# Output_Distribution.net
KiCad netlist of a schematic drawn in Altium Designer
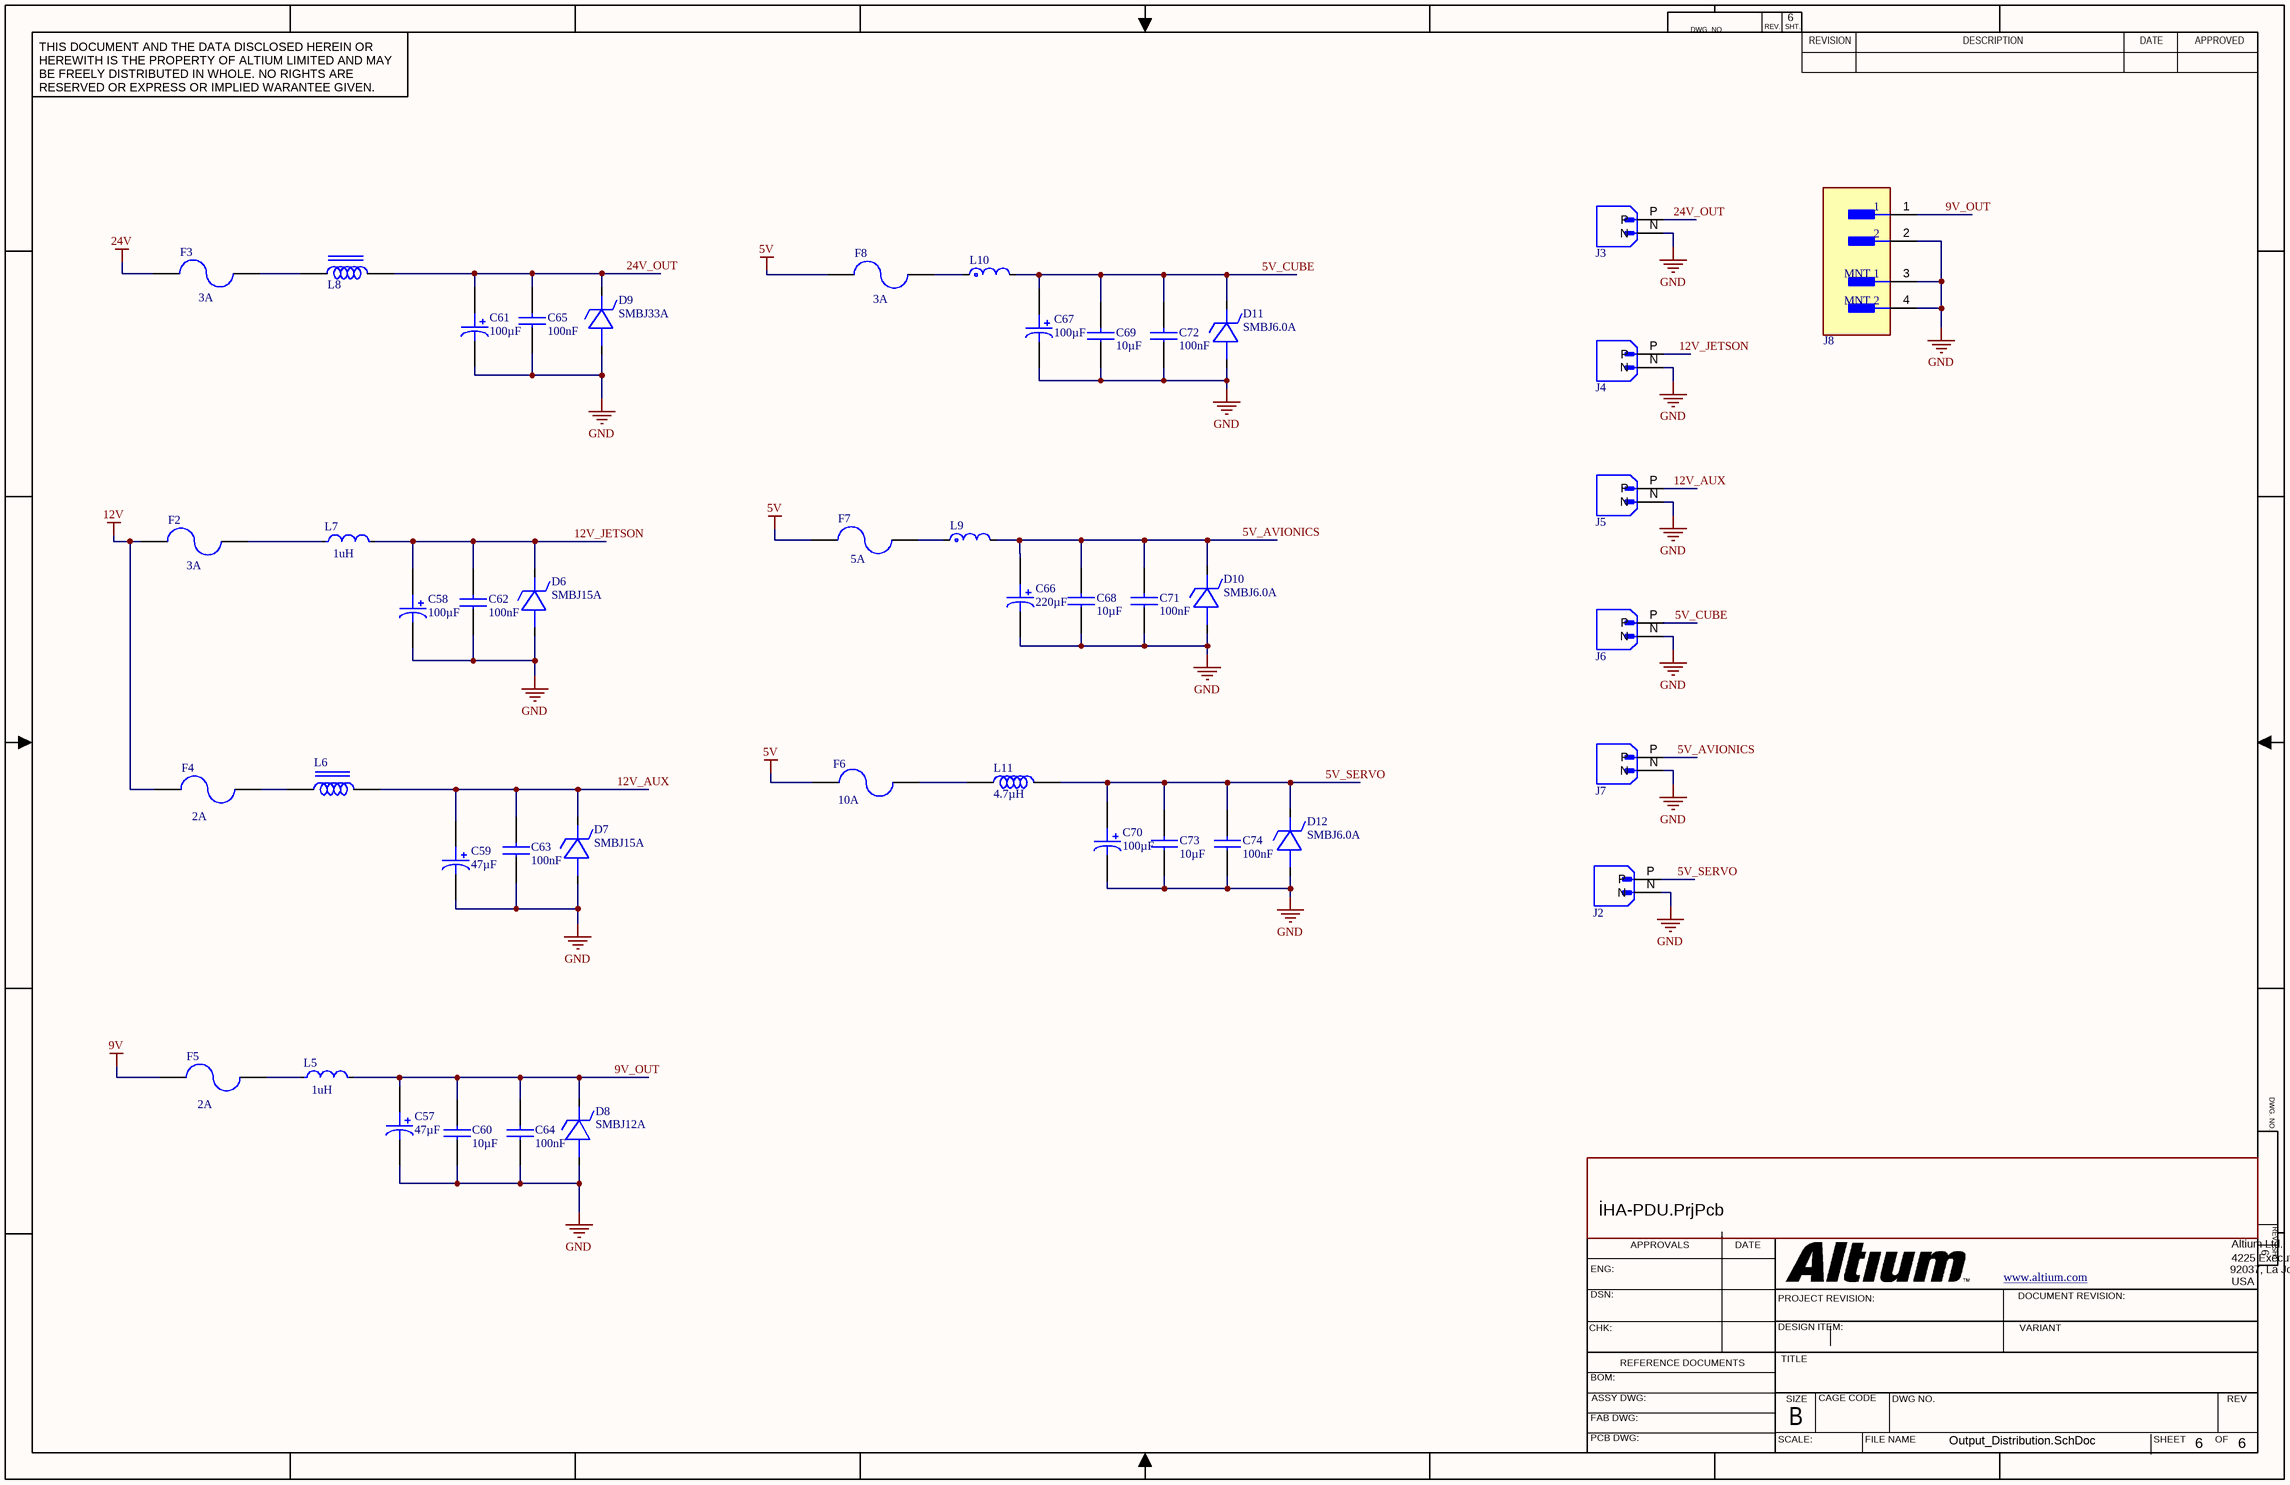
[diagram p0: Output_Distribution.SchDoc]

(export (version "E")
  (design (tool "Eeschema 10.0.6"))
  (components
    (comp (ref "C57")
      (value "47µF")
      (footprint "CAP ALUM SMD")
      (description "47 µF 50 V Aluminum - Polymer Capacitors Radial, Can - SMD 30mOhm 10000 Hrs @ 105°C")
      (fields
        (field (name "MANUFACTURER") "Panasonic")
        (field (name "MANUFACTURER PART NUMBER") "EEH-ZA1H470P")
      )
      (libsource (lib "PDU_BOM") (part "EEH-ZA1H470P"))
    )
    (comp (ref "C58")
      (value "100µF")
      (footprint "CAP ALUM SMD")
      (description "Conductive Polymer Hybrid Aluminum Electrolytic Capacitors, 100µF, 35V, -55 to 105¡C")
      (fields
        (field (name "MANUFACTURER") "Panasonic")
        (field (name "MANUFACTURER PART NUMBER") "EEH-ZA1V101P")
      )
      (libsource (lib "PDU_BOM") (part "EEH-ZA1V101P"))
    )
    (comp (ref "C59")
      (value "47µF")
      (footprint "CAP ALUM SMD")
      (description "47 µF 50 V Aluminum - Polymer Capacitors Radial, Can - SMD 30mOhm 10000 Hrs @ 105°C")
      (fields
        (field (name "MANUFACTURER") "Panasonic")
        (field (name "MANUFACTURER PART NUMBER") "EEH-ZA1H470P")
      )
      (libsource (lib "PDU_BOM") (part "EEH-ZA1H470P"))
    )
    (comp (ref "C60")
      (value "10µF")
      (footprint "CAP_1210_S")
      (description "50V 10uF X5R 卤10% 1210 Multilayer Ceramic Capacitors MLCC - SMD/SMT ROHS")
      (fields
        (field (name "MANUFACTURER") "Samsung Electro-Mechanics")
        (field (name "MANUFACTURER PART NUMBER") "CL32A106KBJNNNE")
      )
      (libsource (lib "PDU_BOM") (part "CL32A106KBJNNNE"))
    )
    (comp (ref "C61")
      (value "100µF")
      (footprint "CAP ALUM SMD")
      (description "Conductive Polymer Hybrid Aluminum Electrolytic Capacitors, 100µF, 35V, -55 to 105¡C")
      (fields
        (field (name "MANUFACTURER") "Panasonic")
        (field (name "MANUFACTURER PART NUMBER") "EEH-ZA1V101P")
      )
      (libsource (lib "PDU_BOM") (part "EEH-ZA1V101P"))
    )
    (comp (ref "C62")
      (value "100nF")
      (footprint "CAP_0603")
      (description "CGA Series 0603 100 nF 50 V ±10 % Tolerance X7R SMT Multilayer Ceramic Capacitor")
      (fields
        (field (name "MANUFACTURER") "TDK")
        (field (name "MANUFACTURER PART NUMBER") "CGA3E2X7R1H104K080AA")
      )
      (libsource (lib "PDU_BOM") (part "CGA3E2X7R1H104K080AA"))
    )
    (comp (ref "C63")
      (value "100nF")
      (footprint "CAP_0603")
      (description "CGA Series 0603 100 nF 50 V ±10 % Tolerance X7R SMT Multilayer Ceramic Capacitor")
      (fields
        (field (name "MANUFACTURER") "TDK")
        (field (name "MANUFACTURER PART NUMBER") "CGA3E2X7R1H104K080AA")
      )
      (libsource (lib "PDU_BOM") (part "CGA3E2X7R1H104K080AA"))
    )
    (comp (ref "C64")
      (value "100nF")
      (footprint "CAP_0603")
      (description "CGA Series 0603 100 nF 50 V ±10 % Tolerance X7R SMT Multilayer Ceramic Capacitor")
      (fields
        (field (name "MANUFACTURER") "TDK")
        (field (name "MANUFACTURER PART NUMBER") "CGA3E2X7R1H104K080AA")
      )
      (libsource (lib "PDU_BOM") (part "CGA3E2X7R1H104K080AA"))
    )
    (comp (ref "C65")
      (value "100nF")
      (footprint "CAP_0603")
      (description "CGA Series 0603 100 nF 50 V ±10 % Tolerance X7R SMT Multilayer Ceramic Capacitor")
      (fields
        (field (name "MANUFACTURER") "TDK")
        (field (name "MANUFACTURER PART NUMBER") "CGA3E2X7R1H104K080AA")
      )
      (libsource (lib "PDU_BOM") (part "CGA3E2X7R1H104K080AA"))
    )
    (comp (ref "C66")
      (value "220µF")
      (footprint "CAP ALUM SMD")
      (description "SMD Polymer Hybrid Aluminum Electrolytic Capacitor, 220uF, 25V, 20%")
      (fields
        (field (name "MANUFACTURER") "Panasonic")
        (field (name "MANUFACTURER PART NUMBER") "EEHZA1E221P")
      )
      (libsource (lib "PDU_BOM") (part "EEHZA1A221P"))
    )
    (comp (ref "C67")
      (value "100µF")
      (footprint "CAP ALUM SMD")
      (description "Conductive Polymer Hybrid Aluminum Electrolytic Capacitors, 100µF, 35V, -55 to 105¡C")
      (fields
        (field (name "MANUFACTURER") "Panasonic")
        (field (name "MANUFACTURER PART NUMBER") "EEH-ZA1V101P")
      )
      (libsource (lib "PDU_BOM") (part "EEH-ZA1V101P"))
    )
    (comp (ref "C68")
      (value "10µF")
      (footprint "CAP_1210_S")
      (description "50V 10uF X5R 卤10% 1210 Multilayer Ceramic Capacitors MLCC - SMD/SMT ROHS")
      (fields
        (field (name "MANUFACTURER") "Samsung Electro-Mechanics")
        (field (name "MANUFACTURER PART NUMBER") "CL32A106KBJNNNE")
      )
      (libsource (lib "PDU_BOM") (part "CL32A106KBJNNNE"))
    )
    (comp (ref "C69")
      (value "10µF")
      (footprint "CAP_1210_S")
      (description "50V 10uF X5R 卤10% 1210 Multilayer Ceramic Capacitors MLCC - SMD/SMT ROHS")
      (fields
        (field (name "MANUFACTURER") "Samsung Electro-Mechanics")
        (field (name "MANUFACTURER PART NUMBER") "CL32A106KBJNNNE")
      )
      (libsource (lib "PDU_BOM") (part "CL32A106KBJNNNE"))
    )
    (comp (ref "C70")
      (value "100µF")
      (footprint "CAP ALUM SMD")
      (description "Conductive Polymer Hybrid Aluminum Electrolytic Capacitors, 100µF, 35V, -55 to 105¡C")
      (fields
        (field (name "MANUFACTURER") "Panasonic")
        (field (name "MANUFACTURER PART NUMBER") "EEH-ZA1V101P")
      )
      (libsource (lib "PDU_BOM") (part "EEH-ZA1V101P"))
    )
    (comp (ref "C71")
      (value "100nF")
      (footprint "CAP_0603")
      (description "CGA Series 0603 100 nF 50 V ±10 % Tolerance X7R SMT Multilayer Ceramic Capacitor")
      (fields
        (field (name "MANUFACTURER") "TDK")
        (field (name "MANUFACTURER PART NUMBER") "CGA3E2X7R1H104K080AA")
      )
      (libsource (lib "PDU_BOM") (part "CGA3E2X7R1H104K080AA"))
    )
    (comp (ref "C72")
      (value "100nF")
      (footprint "CAP_0603")
      (description "CGA Series 0603 100 nF 50 V ±10 % Tolerance X7R SMT Multilayer Ceramic Capacitor")
      (fields
        (field (name "MANUFACTURER") "TDK")
        (field (name "MANUFACTURER PART NUMBER") "CGA3E2X7R1H104K080AA")
      )
      (libsource (lib "PDU_BOM") (part "CGA3E2X7R1H104K080AA"))
    )
    (comp (ref "C73")
      (value "10µF")
      (footprint "CAP_1210_S")
      (description "50V 10uF X5R 卤10% 1210 Multilayer Ceramic Capacitors MLCC - SMD/SMT ROHS")
      (fields
        (field (name "MANUFACTURER") "Samsung Electro-Mechanics")
        (field (name "MANUFACTURER PART NUMBER") "CL32A106KBJNNNE")
      )
      (libsource (lib "PDU_BOM") (part "CL32A106KBJNNNE"))
    )
    (comp (ref "C74")
      (value "100nF")
      (footprint "CAP_0603")
      (description "CGA Series 0603 100 nF 50 V ±10 % Tolerance X7R SMT Multilayer Ceramic Capacitor")
      (fields
        (field (name "MANUFACTURER") "TDK")
        (field (name "MANUFACTURER PART NUMBER") "CGA3E2X7R1H104K080AA")
      )
      (libsource (lib "PDU_BOM") (part "CGA3E2X7R1H104K080AA"))
    )
    (comp (ref "D6")
      (value "SMBJ15A")
      (footprint "SMB (DO-214AA)")
      (description "TVS Diode, SMBJ, Unidirectional, 15 V, 24.4 V, DO-214AA (SMB), 2 Pins")
      (fields (field (name "MANUFACTURER") "Bourns"))
      (libsource (lib "PDU_BOM") (part "SMBJ15A"))
    )
    (comp (ref "D7")
      (value "SMBJ15A")
      (footprint "SMB (DO-214AA)")
      (description "TVS Diode, SMBJ, Unidirectional, 15 V, 24.4 V, DO-214AA (SMB), 2 Pins")
      (fields (field (name "MANUFACTURER") "Bourns"))
      (libsource (lib "PDU_BOM") (part "SMBJ15A"))
    )
    (comp (ref "D8")
      (value "SMBJ12A")
      (footprint "SMB (DO-214AA)")
      (description "SMBJ Series 19.9 V 0.6 kW Surface Mount Uni-Directional TVS Diode - DO-214AA")
      (fields (field (name "MANUFACTURER") "Littelfuse"))
      (libsource (lib "PDU_BOM") (part "SMBJ12A"))
    )
    (comp (ref "D9")
      (value "SMBJ33A")
      (footprint "SMB (DO-214AA)")
      (description "SMBJ Series 53.3 V 0.6 kW Surface Mount Uni-Directional TVS Diode - DO-214AA")
      (fields (field (name "MANUFACTURER") "Littelfuse"))
      (libsource (lib "PDU_BOM") (part "SMBJ33A"))
    )
    (comp (ref "D10")
      (value "SMBJ6.0A")
      (footprint "SMB (DO-214AA)")
      (description "SMBJ Series 10.3 V 0.6 kW Surface Mount Uni-Directional TVS Diode - DO-214AA")
      (fields (field (name "MANUFACTURER") "Littelfuse"))
      (libsource (lib "PDU_BOM") (part "SMBJ6.0A"))
    )
    (comp (ref "D11")
      (value "SMBJ6.0A")
      (footprint "SMB (DO-214AA)")
      (description "SMBJ Series 10.3 V 0.6 kW Surface Mount Uni-Directional TVS Diode - DO-214AA")
      (fields (field (name "MANUFACTURER") "Littelfuse"))
      (libsource (lib "PDU_BOM") (part "SMBJ6.0A"))
    )
    (comp (ref "D12")
      (value "SMBJ6.0A")
      (footprint "SMB (DO-214AA)")
      (description "SMBJ Series 10.3 V 0.6 kW Surface Mount Uni-Directional TVS Diode - DO-214AA")
      (fields (field (name "MANUFACTURER") "Littelfuse"))
      (libsource (lib "PDU_BOM") (part "SMBJ6.0A"))
    )
    (comp (ref "F2")
      (value "Littelfuse 0452003.MRL")
      (footprint "FUSE_2410")
      (description "Fuse Chip Slow Blow Acting 3A 125V SMD Solder Pad 2410 Ceramic T/R CSA/PSE/UL")
      (fields
        (field (name "MANUFACTURER") "Littelfuse")
        (field (name "MANUFACTURER PART NUMBER") "0452003.MRL")
        (field (name "CURRENT RATING") "3A")
      )
      (libsource (lib "PDU_BOM") (part "Littelfuse 0452003.MRL"))
    )
    (comp (ref "F3")
      (value "Littelfuse 0452003.MRL")
      (footprint "FUSE_2410")
      (description "Fuse Chip Slow Blow Acting 3A 125V SMD Solder Pad 2410 Ceramic T/R CSA/PSE/UL")
      (fields
        (field (name "MANUFACTURER") "Littelfuse")
        (field (name "MANUFACTURER PART NUMBER") "0452003.MRL")
        (field (name "CURRENT RATING") "3A")
      )
      (libsource (lib "PDU_BOM") (part "Littelfuse 0452003.MRL"))
    )
    (comp (ref "F4")
      (value "Littelfuse 0452002.MRL")
      (footprint "FUSE_2410")
      (description "452 Series - NANO2®Slo-Blo®Subminiature Surface Mount Fuse, 2 A, 125 VAC 125 VDC, RoHS")
      (fields
        (field (name "MANUFACTURER") "Littelfuse")
        (field (name "MANUFACTURER PART NUMBER") "0452002.MRL")
        (field (name "FUSE CURRENT") "2A")
      )
      (libsource (lib "PDU_BOM") (part "Littelfuse 0452002.MRL"))
    )
    (comp (ref "F5")
      (value "Littelfuse 0452002.MRL")
      (footprint "FUSE_2410")
      (description "452 Series - NANO2®Slo-Blo®Subminiature Surface Mount Fuse, 2 A, 125 VAC 125 VDC, RoHS")
      (fields
        (field (name "MANUFACTURER") "Littelfuse")
        (field (name "MANUFACTURER PART NUMBER") "0452002.MRL")
        (field (name "FUSE CURRENT") "2A")
      )
      (libsource (lib "PDU_BOM") (part "Littelfuse 0452002.MRL"))
    )
    (comp (ref "F6")
      (value "Littelfuse 0452010.MRL")
      (footprint "FUSE_2410")
      (description "Electric Fuse, Time Lag Blow, 10A, 72VAC, 60VDC, 50A (IR), Surface Mount, NANO")
      (fields
        (field (name "MANUFACTURER") "Littelfuse")
        (field (name "MANUFACTURER PART NUMBER") "0452010.MRL")
        (field (name "CURRENT RATING") "10A")
      )
      (libsource (lib "PDU_BOM") (part "Littelfuse 0452010.MRL"))
    )
    (comp (ref "F7")
      (value "Littelfuse 0452005.MRL")
      (footprint "FUSE_2410")
      (description "452 Series - NANO2®Slo-Blo®Subminiature Surface Mount Fuse, 5 A, 125 VAC 125 VDC, RoHS")
      (fields
        (field (name "MANUFACTURER") "Littelfuse")
        (field (name "MANUFACTURER PART NUMBER") "0452005.MRL")
        (field (name "FUSE CURRENT") "5A")
      )
      (libsource (lib "PDU_BOM") (part "Littelfuse 0452005.MRL"))
    )
    (comp (ref "F8")
      (value "Littelfuse 0452003.MRL")
      (footprint "FUSE_2410")
      (description "Fuse Chip Slow Blow Acting 3A 125V SMD Solder Pad 2410 Ceramic T/R CSA/PSE/UL")
      (fields
        (field (name "MANUFACTURER") "Littelfuse")
        (field (name "MANUFACTURER PART NUMBER") "0452003.MRL")
        (field (name "CURRENT RATING") "3A")
      )
      (libsource (lib "PDU_BOM") (part "Littelfuse 0452003.MRL"))
    )
    (comp (ref "J2")
      (value "XT30PW-M")
      (footprint "XT30PW-M")
      (description "Socket; DC supply; XT30; male; PIN: 2; on PCBs; THT; Colour: yellow")
      (libsource (lib "") (part "XT30PW-M_1"))
    )
    (comp (ref "J3")
      (value "XT30PW-M")
      (footprint "XT30PW-M")
      (description "Socket; DC supply; XT30; male; PIN: 2; on PCBs; THT; Colour: yellow")
      (libsource (lib "") (part "XT30PW-M_1"))
    )
    (comp (ref "J4")
      (value "XT30PW-M")
      (footprint "XT30PW-M")
      (description "Socket; DC supply; XT30; male; PIN: 2; on PCBs; THT; Colour: yellow")
      (libsource (lib "PDU_BOM") (part "XT30PW-M"))
    )
    (comp (ref "J5")
      (value "XT30PW-M")
      (footprint "XT30PW-M")
      (description "Socket; DC supply; XT30; male; PIN: 2; on PCBs; THT; Colour: yellow")
      (libsource (lib "") (part "XT30PW-M_1"))
    )
    (comp (ref "J6")
      (value "XT30PW-M")
      (footprint "XT30PW-M")
      (description "Socket; DC supply; XT30; male; PIN: 2; on PCBs; THT; Colour: yellow")
      (libsource (lib "PDU_BOM") (part "XT30PW-M"))
    )
    (comp (ref "J7")
      (value "XT30PW-M")
      (footprint "XT30PW-M")
      (description "Socket; DC supply; XT30; male; PIN: 2; on PCBs; THT; Colour: yellow")
      (libsource (lib "") (part "XT30PW-M_1"))
    )
    (comp (ref "J8")
      (value "SM02B-GHS-TB")
      (footprint "SM02B-GHS-TB")
      (description "MCU 32-bit LPC1800 ARM Cortex M3 RISC 768KB Flash 3.3V 100-Pin TFBGA Tray")
      (fields
        (field (name "MANUFACTURER") "JST")
        (field (name "MANUFACTURER PART NUMBER") "SM02B-GHS-TB(LF)(SN)")
      )
      (libsource (lib "PDU_BOM") (part "SM02B-GHS-TB"))
    )
    (comp (ref "L5")
      (value "1uH")
      (footprint "FP-XAL4020-102MEC-MFG")
      (description "Fixed Inductors 1uH 20% 9.6A 14.60mOhms AEC-Q200")
      (fields
        (field (name "MANUFACTURER") "Coilcraft")
        (field (name "OCTOPART") "https://octopart.com/xal4020-102mec-coilcraft-13142161")
      )
      (libsource (lib "Altium Content Vault") (part "725321dda6339637d4d059423bc1c3c"))
    )
    (comp (ref "L6")
      (value "BLM31PG601SN1L")
      (footprint "CAP_1206")
      (description "Ferrite Beads Multi-Layer 600Ohm 25% 100MHz 1.5A 80mOhm DCR 1206 Embossed T/R")
      (fields (field (name "MANUFACTURER") "Murata") (field (name "TOLERANCE") "25%"))
      (libsource (lib "PDU_BOM") (part "BLM31PG601SN1L"))
    )
    (comp (ref "L7")
      (value "1uH")
      (footprint "FP-XAL4020-102MEC-MFG")
      (description "Fixed Inductors 1uH 20% 9.6A 14.60mOhms AEC-Q200")
      (fields
        (field (name "MANUFACTURER") "Coilcraft")
        (field (name "OCTOPART") "https://octopart.com/xal4020-102mec-coilcraft-13142161")
      )
      (libsource (lib "Altium Content Vault") (part "725321dda6339637d4d059423bc1c3c"))
    )
    (comp (ref "L8")
      (value "BLM31SN500SH1L")
      (footprint "CAP_1206")
      (description "Ferrite Beads Multi-Layer Power 50Ohm 25% 100MHz 12A 0.0016Ohm DCR 1206 Automotive T/R")
      (fields (field (name "MANUFACTURER") "Murata") (field (name "TOLERANCE") "25%"))
      (libsource (lib "PDU_BOM") (part "BLM31SN500SH1L"))
    )
    (comp (ref "L9")
      (value "XAL5030-222MEC")
      (footprint "FP-XAL5030-222MEC-MFG")
      (description "Fixed Inductors 2.2uH Shld 20% 9.2A 14.5mOhms AECQ2 SRF: 38MHz Test Freq: 1MHz")
      (fields (field (name "TOLERANCE") "20%"))
      (libsource (lib "Altium Content Vault") (part "4cc4b267dca4c8e51f7102f422741d8"))
    )
    (comp (ref "L10")
      (value "XAL5030-222MEC")
      (footprint "FP-XAL5030-222MEC-MFG")
      (description "Fixed Inductors 2.2uH Shld 20% 9.2A 14.5mOhms AECQ2 SRF: 38MHz Test Freq: 1MHz")
      (fields (field (name "TOLERANCE") "20%"))
      (libsource (lib "Altium Content Vault") (part "4cc4b267dca4c8e51f7102f422741d8"))
    )
    (comp (ref "L11")
      (value "4.7µH")
      (footprint "XAL6060")
      (description "Güç İndüktörleri - SMD 4.7uH Shld 20% 11A 14.4mOhms AECQ2")
      (fields
        (field (name "MANUFACTURER") "Coilcraft")
        (field (name "MANUFACTURER PART NUMBER") "XAL6060-472MEB")
      )
      (libsource (lib "PDU_BOM") (part "XAL6060-472MEB"))
    )
  )
  (nets
    (net (code "1") (name "/5V_AVIONICS") (class "Default")
      (node (ref "C66") (pin "1") (pinfunction "C_1") (pintype "passive"))
      (node (ref "C68") (pin "2") (pinfunction "2_2") (pintype "passive"))
      (node (ref "C71") (pin "2") (pinfunction "2_2") (pintype "passive"))
      (node (ref "D10") (pin "1") (pinfunction "1_1") (pintype "passive"))
      (node (ref "J7") (pin "P") (pinfunction "P_P") (pintype "power_in"))
      (node (ref "L9") (pin "2") (pinfunction "2_2") (pintype "passive"))
    )
    (net (code "2") (name "/5V_CUBE") (class "Default")
      (node (ref "C67") (pin "1") (pinfunction "C_1") (pintype "passive"))
      (node (ref "C69") (pin "2") (pinfunction "2_2") (pintype "passive"))
      (node (ref "C72") (pin "2") (pinfunction "2_2") (pintype "passive"))
      (node (ref "D11") (pin "1") (pinfunction "1_1") (pintype "passive"))
      (node (ref "J6") (pin "P") (pinfunction "P_P") (pintype "power_in"))
      (node (ref "L10") (pin "2") (pinfunction "2_2") (pintype "passive"))
    )
    (net (code "3") (name "/5V_SERVO") (class "Default")
      (node (ref "C70") (pin "1") (pinfunction "C_1") (pintype "passive"))
      (node (ref "C73") (pin "2") (pinfunction "2_2") (pintype "passive"))
      (node (ref "C74") (pin "2") (pinfunction "2_2") (pintype "passive"))
      (node (ref "D12") (pin "1") (pinfunction "1_1") (pintype "passive"))
      (node (ref "J2") (pin "P") (pinfunction "P_P") (pintype "power_in"))
      (node (ref "L11") (pin "2") (pinfunction "2_2") (pintype "passive"))
    )
    (net (code "4") (name "/9V_OUT") (class "Default")
      (node (ref "C57") (pin "1") (pinfunction "C_1") (pintype "passive"))
      (node (ref "C60") (pin "2") (pinfunction "2_2") (pintype "passive"))
      (node (ref "C64") (pin "2") (pinfunction "2_2") (pintype "passive"))
      (node (ref "D8") (pin "1") (pinfunction "1_1") (pintype "passive"))
      (node (ref "J8") (pin "1") (pinfunction "1_1") (pintype "passive"))
      (node (ref "L5") (pin "2") (pinfunction "2_2") (pintype "passive"))
    )
    (net (code "5") (name "/12V_AUX") (class "Default")
      (node (ref "C59") (pin "1") (pinfunction "C_1") (pintype "passive"))
      (node (ref "C63") (pin "2") (pinfunction "2_2") (pintype "passive"))
      (node (ref "D7") (pin "1") (pinfunction "1_1") (pintype "passive"))
      (node (ref "J5") (pin "P") (pinfunction "P_P") (pintype "power_in"))
      (node (ref "L6") (pin "2") (pinfunction "2_2") (pintype "passive"))
    )
    (net (code "6") (name "/12V_JETSON") (class "Default")
      (node (ref "C58") (pin "1") (pinfunction "C_1") (pintype "passive"))
      (node (ref "C62") (pin "2") (pinfunction "2_2") (pintype "passive"))
      (node (ref "D6") (pin "1") (pinfunction "1_1") (pintype "passive"))
      (node (ref "J4") (pin "P") (pinfunction "P_P") (pintype "power_in"))
      (node (ref "L7") (pin "2") (pinfunction "2_2") (pintype "passive"))
    )
    (net (code "7") (name "/24V_OUT") (class "Default")
      (node (ref "C61") (pin "1") (pinfunction "C_1") (pintype "passive"))
      (node (ref "C65") (pin "2") (pinfunction "2_2") (pintype "passive"))
      (node (ref "D9") (pin "1") (pinfunction "1_1") (pintype "passive"))
      (node (ref "J3") (pin "P") (pinfunction "P_P") (pintype "power_in"))
      (node (ref "L8") (pin "2") (pinfunction "2_2") (pintype "passive"))
    )
    (net (code "8") (name "5V") (class "Default")
      (node (ref "F6") (pin "1") (pinfunction "1_1") (pintype "passive"))
      (node (ref "F7") (pin "1") (pinfunction "1_1") (pintype "passive"))
      (node (ref "F8") (pin "1") (pinfunction "1_1") (pintype "passive"))
    )
    (net (code "9") (name "9V") (class "Default")
      (node (ref "F5") (pin "1") (pinfunction "1_1") (pintype "passive"))
    )
    (net (code "10") (name "12V") (class "Default")
      (node (ref "F2") (pin "1") (pinfunction "1_1") (pintype "passive"))
      (node (ref "F4") (pin "1") (pinfunction "1_1") (pintype "passive"))
    )
    (net (code "11") (name "24V") (class "Default")
      (node (ref "F3") (pin "1") (pinfunction "1_1") (pintype "passive"))
    )
    (net (code "12") (name "GND") (class "Default")
      (node (ref "C57") (pin "2") (pinfunction "A_2") (pintype "passive"))
      (node (ref "C58") (pin "2") (pinfunction "A_2") (pintype "passive"))
      (node (ref "C59") (pin "2") (pinfunction "A_2") (pintype "passive"))
      (node (ref "C60") (pin "1") (pinfunction "1_1") (pintype "passive"))
      (node (ref "C61") (pin "2") (pinfunction "A_2") (pintype "passive"))
      (node (ref "C62") (pin "1") (pinfunction "1_1") (pintype "passive"))
      (node (ref "C63") (pin "1") (pinfunction "1_1") (pintype "passive"))
      (node (ref "C64") (pin "1") (pinfunction "1_1") (pintype "passive"))
      (node (ref "C65") (pin "1") (pinfunction "1_1") (pintype "passive"))
      (node (ref "C66") (pin "2") (pinfunction "A_2") (pintype "passive"))
      (node (ref "C67") (pin "2") (pinfunction "A_2") (pintype "passive"))
      (node (ref "C68") (pin "1") (pinfunction "1_1") (pintype "passive"))
      (node (ref "C69") (pin "1") (pinfunction "1_1") (pintype "passive"))
      (node (ref "C70") (pin "2") (pinfunction "A_2") (pintype "passive"))
      (node (ref "C71") (pin "1") (pinfunction "1_1") (pintype "passive"))
      (node (ref "C72") (pin "1") (pinfunction "1_1") (pintype "passive"))
      (node (ref "C73") (pin "1") (pinfunction "1_1") (pintype "passive"))
      (node (ref "C74") (pin "1") (pinfunction "1_1") (pintype "passive"))
      (node (ref "D10") (pin "2") (pinfunction "2_2") (pintype "passive"))
      (node (ref "D11") (pin "2") (pinfunction "2_2") (pintype "passive"))
      (node (ref "D12") (pin "2") (pinfunction "2_2") (pintype "passive"))
      (node (ref "D6") (pin "2") (pinfunction "2_2") (pintype "passive"))
      (node (ref "D7") (pin "2") (pinfunction "2_2") (pintype "passive"))
      (node (ref "D8") (pin "2") (pinfunction "2_2") (pintype "passive"))
      (node (ref "D9") (pin "2") (pinfunction "2_2") (pintype "passive"))
      (node (ref "J2") (pin "N") (pinfunction "N_N") (pintype "power_in"))
      (node (ref "J3") (pin "N") (pinfunction "N_N") (pintype "power_in"))
      (node (ref "J4") (pin "N") (pinfunction "N_N") (pintype "power_in"))
      (node (ref "J5") (pin "N") (pinfunction "N_N") (pintype "power_in"))
      (node (ref "J6") (pin "N") (pinfunction "N_N") (pintype "power_in"))
      (node (ref "J7") (pin "N") (pinfunction "N_N") (pintype "power_in"))
      (node (ref "J8") (pin "2") (pinfunction "2_2") (pintype "passive"))
      (node (ref "J8") (pin "3") (pinfunction "MNT_1_3") (pintype "passive"))
      (node (ref "J8") (pin "4") (pinfunction "MNT_2_4") (pintype "passive"))
    )
    (net (code "13") (name "Net-(F2-Pad2)") (class "Default")
      (node (ref "F2") (pin "2") (pinfunction "2_2") (pintype "passive"))
      (node (ref "L7") (pin "1") (pinfunction "1_1") (pintype "passive"))
    )
    (net (code "14") (name "Net-(F3-Pad2)") (class "Default")
      (node (ref "F3") (pin "2") (pinfunction "2_2") (pintype "passive"))
      (node (ref "L8") (pin "1") (pinfunction "1_1") (pintype "passive"))
    )
    (net (code "15") (name "Net-(F4-Pad2)") (class "Default")
      (node (ref "F4") (pin "2") (pinfunction "2_2") (pintype "passive"))
      (node (ref "L6") (pin "1") (pinfunction "1_1") (pintype "passive"))
    )
    (net (code "16") (name "Net-(F5-Pad2)") (class "Default")
      (node (ref "F5") (pin "2") (pinfunction "2_2") (pintype "passive"))
      (node (ref "L5") (pin "1") (pinfunction "1_1") (pintype "passive"))
    )
    (net (code "17") (name "Net-(F6-Pad2)") (class "Default")
      (node (ref "F6") (pin "2") (pinfunction "2_2") (pintype "passive"))
      (node (ref "L11") (pin "1") (pinfunction "1_1") (pintype "passive"))
    )
    (net (code "18") (name "Net-(F7-Pad2)") (class "Default")
      (node (ref "F7") (pin "2") (pinfunction "2_2") (pintype "passive"))
      (node (ref "L9") (pin "1") (pinfunction "1_1") (pintype "passive"))
    )
    (net (code "19") (name "Net-(F8-Pad2)") (class "Default")
      (node (ref "F8") (pin "2") (pinfunction "2_2") (pintype "passive"))
      (node (ref "L10") (pin "1") (pinfunction "1_1") (pintype "passive"))
    )
  )
)
